# openTPM-v20.net
KiCad netlist of a schematic drawn in EAGLE
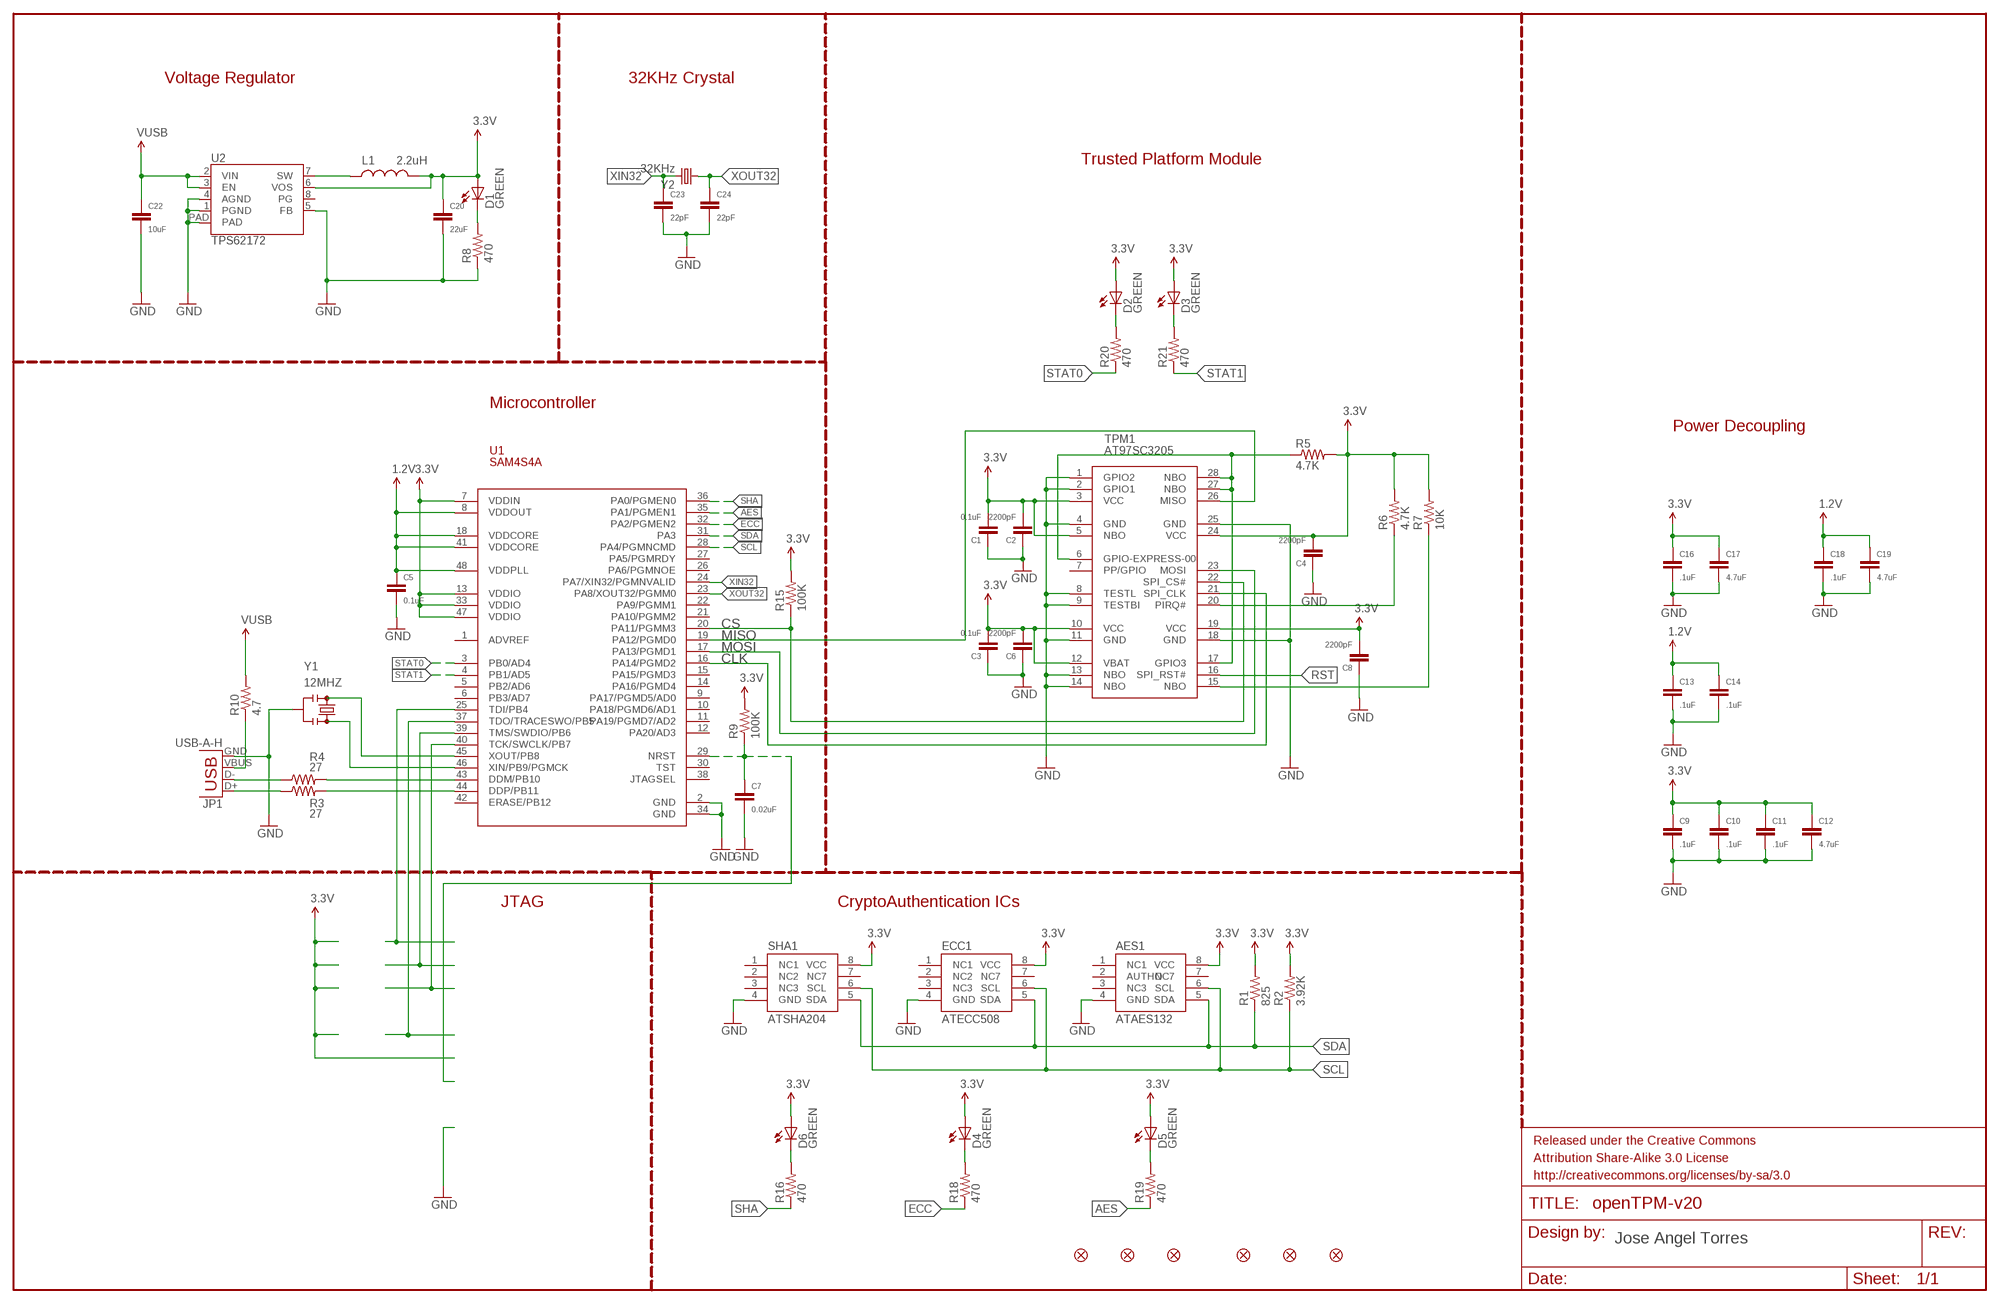
[diagram p0: schematic, sheet 1]

(export (version "E")
  (design (tool "Eeschema 10.0.6"))
  (components
    (comp (ref "AES1")
      (value "ATAES132")
      (footprint "eagle-import:CRYPTOTRONIX_SOIC8")
      (libsource (lib "eagle-import") (part "CRYPTOTRONIX_ATAES132"))
    )
    (comp (ref "C1")
      (value "0.1uF")
      (footprint "eagle-import:0402")
      (libsource (lib "eagle-import") (part "CAPACITOR.0402"))
    )
    (comp (ref "C2")
      (value "2200pF")
      (footprint "eagle-import:0402")
      (libsource (lib "eagle-import") (part "CAPACITOR.0402"))
    )
    (comp (ref "C3")
      (value "0.1uF")
      (footprint "eagle-import:0402")
      (libsource (lib "eagle-import") (part "CAPACITOR.0402"))
    )
    (comp (ref "C4")
      (value "2200pF")
      (footprint "eagle-import:0402")
      (libsource (lib "eagle-import") (part "CAPACITOR.0402"))
    )
    (comp (ref "C5")
      (value "0.1uF")
      (footprint "eagle-import:0402")
      (libsource (lib "eagle-import") (part "CAPACITOR.0402"))
    )
    (comp (ref "C6")
      (value "2200pF")
      (footprint "eagle-import:0402")
      (libsource (lib "eagle-import") (part "CAPACITOR.0402"))
    )
    (comp (ref "C7")
      (value "0.02uF")
      (footprint "eagle-import:0402")
      (libsource (lib "eagle-import") (part "CAPACITOR.0402"))
    )
    (comp (ref "C8")
      (value "2200pF")
      (footprint "eagle-import:0402")
      (libsource (lib "eagle-import") (part "CAPACITOR.0402"))
    )
    (comp (ref "C9")
      (value ".1uF")
      (footprint "eagle-import:0402")
      (libsource (lib "eagle-import") (part "CAPACITOR.0402"))
    )
    (comp (ref "C10")
      (value ".1uF")
      (footprint "eagle-import:0402")
      (libsource (lib "eagle-import") (part "CAPACITOR.0402"))
    )
    (comp (ref "C11")
      (value ".1uF")
      (footprint "eagle-import:0402")
      (libsource (lib "eagle-import") (part "CAPACITOR.0402"))
    )
    (comp (ref "C12")
      (value "4.7uF")
      (footprint "eagle-import:0402")
      (libsource (lib "eagle-import") (part "CAPACITOR.0402"))
    )
    (comp (ref "C13")
      (value ".1uF")
      (footprint "eagle-import:0402")
      (libsource (lib "eagle-import") (part "CAPACITOR.0402"))
    )
    (comp (ref "C14")
      (value ".1uF")
      (footprint "eagle-import:0402")
      (libsource (lib "eagle-import") (part "CAPACITOR.0402"))
    )
    (comp (ref "C16")
      (value ".1uF")
      (footprint "eagle-import:0402")
      (libsource (lib "eagle-import") (part "CAPACITOR.0402"))
    )
    (comp (ref "C17")
      (value "4.7uF")
      (footprint "eagle-import:0402")
      (libsource (lib "eagle-import") (part "CAPACITOR.0402"))
    )
    (comp (ref "C18")
      (value ".1uF")
      (footprint "eagle-import:0402")
      (libsource (lib "eagle-import") (part "CAPACITOR.0402"))
    )
    (comp (ref "C19")
      (value "4.7uF")
      (footprint "eagle-import:0402")
      (libsource (lib "eagle-import") (part "CAPACITOR.0402"))
    )
    (comp (ref "C20")
      (value "22uF")
      (footprint "eagle-import:0603")
      (libsource (lib "eagle-import") (part "CAPACITOR.0603"))
    )
    (comp (ref "C22")
      (value "10uF")
      (footprint "eagle-import:0402")
      (libsource (lib "eagle-import") (part "CAPACITOR.0402"))
    )
    (comp (ref "C23")
      (value "22pF")
      (footprint "eagle-import:0402")
      (libsource (lib "eagle-import") (part "CAPACITOR.0402"))
    )
    (comp (ref "C24")
      (value "22pF")
      (footprint "eagle-import:0402")
      (libsource (lib "eagle-import") (part "CAPACITOR.0402"))
    )
    (comp (ref "D1")
      (value "GREEN")
      (footprint "eagle-import:SPARKFUN-LED_LED-0603")
      (libsource (lib "eagle-import") (part "SPARKFUN-LED_LED-GREEN0603"))
    )
    (comp (ref "D2")
      (value "GREEN")
      (footprint "eagle-import:SPARKFUN-LED_LED-0603")
      (libsource (lib "eagle-import") (part "SPARKFUN-LED_LED-GREEN0603"))
    )
    (comp (ref "D3")
      (value "GREEN")
      (footprint "eagle-import:SPARKFUN-LED_LED-0603")
      (libsource (lib "eagle-import") (part "SPARKFUN-LED_LED-GREEN0603"))
    )
    (comp (ref "D4")
      (value "GREEN")
      (footprint "eagle-import:SPARKFUN-LED_LED-0603")
      (libsource (lib "eagle-import") (part "SPARKFUN-LED_LED-GREEN0603"))
    )
    (comp (ref "D5")
      (value "GREEN")
      (footprint "eagle-import:SPARKFUN-LED_LED-0603")
      (libsource (lib "eagle-import") (part "SPARKFUN-LED_LED-GREEN0603"))
    )
    (comp (ref "D6")
      (value "GREEN")
      (footprint "eagle-import:SPARKFUN-LED_LED-0603")
      (libsource (lib "eagle-import") (part "SPARKFUN-LED_LED-GREEN0603"))
    )
    (comp (ref "ECC1")
      (value "ATECC508")
      (footprint "eagle-import:CRYPTOTRONIX_SOIC8")
      (libsource (lib "eagle-import") (part "ATECC508"))
    )
    (comp (ref "FID1")
      (value "SPARKFUN-AESTHETICS_FIDUCIAL1X2")
      (footprint "eagle-import:SPARKFUN-AESTHETICS_FIDUCIAL-1X2")
      (libsource (lib "eagle-import") (part "SPARKFUN-AESTHETICS_FIDUCIAL1X2"))
    )
    (comp (ref "FID2")
      (value "SPARKFUN-AESTHETICS_FIDUCIAL1X2")
      (footprint "eagle-import:SPARKFUN-AESTHETICS_FIDUCIAL-1X2")
      (libsource (lib "eagle-import") (part "SPARKFUN-AESTHETICS_FIDUCIAL1X2"))
    )
    (comp (ref "FID3")
      (value "SPARKFUN-AESTHETICS_FIDUCIAL1X2")
      (footprint "eagle-import:SPARKFUN-AESTHETICS_FIDUCIAL-1X2")
      (libsource (lib "eagle-import") (part "SPARKFUN-AESTHETICS_FIDUCIAL1X2"))
    )
    (comp (ref "FID4")
      (value "SPARKFUN-AESTHETICS_FIDUCIAL1X2")
      (footprint "eagle-import:SPARKFUN-AESTHETICS_FIDUCIAL-1X2")
      (libsource (lib "eagle-import") (part "SPARKFUN-AESTHETICS_FIDUCIAL1X2"))
    )
    (comp (ref "FID5")
      (value "SPARKFUN-AESTHETICS_FIDUCIAL1X2")
      (footprint "eagle-import:SPARKFUN-AESTHETICS_FIDUCIAL-1X2")
      (libsource (lib "eagle-import") (part "SPARKFUN-AESTHETICS_FIDUCIAL1X2"))
    )
    (comp (ref "FID6")
      (value "SPARKFUN-AESTHETICS_FIDUCIAL1X2")
      (footprint "eagle-import:SPARKFUN-AESTHETICS_FIDUCIAL-1X2")
      (libsource (lib "eagle-import") (part "SPARKFUN-AESTHETICS_FIDUCIAL1X2"))
    )
    (comp (ref "JP1")
      (value "USB-A-H")
      (footprint "eagle-import:USB-A-H")
      (libsource (lib "eagle-import") (part "USB-A-H"))
    )
    (comp (ref "L1")
      (value "2.2uH")
      (footprint "eagle-import:C0402")
      (libsource (lib "eagle-import") (part "INDUCTOR0402"))
    )
    (comp (ref "R1")
      (value "825")
      (footprint "eagle-import:0402")
      (libsource (lib "eagle-import") (part "RESISTOR.0402"))
    )
    (comp (ref "R2")
      (value "3.92K")
      (footprint "eagle-import:0402")
      (libsource (lib "eagle-import") (part "RESISTOR.0402"))
    )
    (comp (ref "R3")
      (value "27")
      (footprint "eagle-import:0402")
      (libsource (lib "eagle-import") (part "RESISTOR.0402"))
    )
    (comp (ref "R4")
      (value "27")
      (footprint "eagle-import:0402")
      (libsource (lib "eagle-import") (part "RESISTOR.0402"))
    )
    (comp (ref "R5")
      (value "4.7K")
      (footprint "eagle-import:0402")
      (libsource (lib "eagle-import") (part "RESISTOR.0402"))
    )
    (comp (ref "R6")
      (value "4.7K")
      (footprint "eagle-import:0402")
      (libsource (lib "eagle-import") (part "RESISTOR.0402"))
    )
    (comp (ref "R7")
      (value "10K")
      (footprint "eagle-import:0402")
      (libsource (lib "eagle-import") (part "RESISTOR.0402"))
    )
    (comp (ref "R8")
      (value "470")
      (footprint "eagle-import:0402")
      (libsource (lib "eagle-import") (part "RESISTOR.0402"))
    )
    (comp (ref "R9")
      (value "100K")
      (footprint "eagle-import:0402")
      (libsource (lib "eagle-import") (part "RESISTOR.0402"))
    )
    (comp (ref "R10")
      (value "4.7")
      (footprint "eagle-import:0402")
      (libsource (lib "eagle-import") (part "RESISTOR.0402"))
    )
    (comp (ref "R15")
      (value "100K")
      (footprint "eagle-import:0402")
      (libsource (lib "eagle-import") (part "RESISTOR.0402"))
    )
    (comp (ref "R16")
      (value "470")
      (footprint "eagle-import:0402")
      (libsource (lib "eagle-import") (part "RESISTOR.0402"))
    )
    (comp (ref "R18")
      (value "470")
      (footprint "eagle-import:0402")
      (libsource (lib "eagle-import") (part "RESISTOR.0402"))
    )
    (comp (ref "R19")
      (value "470")
      (footprint "eagle-import:0402")
      (libsource (lib "eagle-import") (part "RESISTOR.0402"))
    )
    (comp (ref "R20")
      (value "470")
      (footprint "eagle-import:0402")
      (libsource (lib "eagle-import") (part "RESISTOR.0402"))
    )
    (comp (ref "R21")
      (value "470")
      (footprint "eagle-import:0402")
      (libsource (lib "eagle-import") (part "RESISTOR.0402"))
    )
    (comp (ref "SHA1")
      (value "ATSHA204")
      (footprint "eagle-import:CRYPTOTRONIX_SOIC8")
      (libsource (lib "eagle-import") (part "CRYPTOTRONIX_ATSHA204"))
    )
    (comp (ref "TPM1")
      (value "AT97SC3205")
      (footprint "eagle-import:TSSOP28")
      (libsource (lib "eagle-import") (part "AT97SC3205"))
    )
    (comp (ref "U1")
      (value "SAM4S4A")
      (footprint "eagle-import:LQFP-48")
      (libsource (lib "eagle-import") (part "SAM4S4A"))
    )
    (comp (ref "U2")
      (value "TPS62172")
      (footprint "eagle-import:WSON-8-PAD")
      (libsource (lib "eagle-import") (part "TPS62172"))
    )
    (comp (ref "Y1")
      (value "12MHZ")
      (footprint "eagle-import:RESONATOR-SMD")
      (libsource (lib "eagle-import") (part "RESONATOR12MHZ"))
    )
    (comp (ref "Y2")
      (value "32KHz")
      (footprint "eagle-import:CRYSTAL-32KHZ-SMD_EPSON_MC146")
      (libsource (lib "eagle-import") (part "CRYSTALEPSONMC146"))
    )
  )
  (nets
    (net (code "1") (name "/CLK") (class "Default")
      (node (ref "TPM1") (pin "21") (pinfunction "SPI_CLK_21") (pintype "bidirectional"))
      (node (ref "U1") (pin "16") (pinfunction "PA14/PGMD2_16") (pintype "bidirectional"))
    )
    (net (code "2") (name "/CS") (class "Default")
      (node (ref "R15") (pin "1") (pinfunction "1_1") (pintype "passive"))
      (node (ref "TPM1") (pin "22") (pinfunction "SPI_CS#_22") (pintype "power_in"))
      (node (ref "U1") (pin "20") (pinfunction "PA11/PGMM3_20") (pintype "bidirectional"))
    )
    (net (code "3") (name "/MISO") (class "Default")
      (node (ref "TPM1") (pin "26") (pinfunction "MISO_26") (pintype "power_in"))
      (node (ref "U1") (pin "19") (pinfunction "PA12/PGMD0_19") (pintype "bidirectional"))
    )
    (net (code "4") (name "/MOSI") (class "Default")
      (node (ref "TPM1") (pin "23") (pinfunction "MOSI_23") (pintype "power_in"))
      (node (ref "U1") (pin "17") (pinfunction "PA13/PGMD1_17") (pintype "bidirectional"))
    )
    (net (code "5") (name "1.2V") (class "Default")
      (node (ref "C13") (pin "1") (pinfunction "1_1") (pintype "passive"))
      (node (ref "C14") (pin "1") (pinfunction "1_1") (pintype "passive"))
      (node (ref "C18") (pin "1") (pinfunction "1_1") (pintype "passive"))
      (node (ref "C19") (pin "1") (pinfunction "1_1") (pintype "passive"))
      (node (ref "C5") (pin "1") (pinfunction "1_1") (pintype "passive"))
      (node (ref "U1") (pin "18") (pinfunction "VDDCORE_18") (pintype "bidirectional"))
      (node (ref "U1") (pin "41") (pinfunction "VDDCORE_41") (pintype "bidirectional"))
      (node (ref "U1") (pin "48") (pinfunction "VDDPLL_48") (pintype "bidirectional"))
      (node (ref "U1") (pin "8") (pinfunction "VDDOUT_8") (pintype "bidirectional"))
    )
    (net (code "6") (name "3.3V") (class "Default")
      (node (ref "AES1") (pin "8") (pinfunction "VCC_8") (pintype "power_in"))
      (node (ref "C1") (pin "2") (pinfunction "2_2") (pintype "passive"))
      (node (ref "C10") (pin "1") (pinfunction "1_1") (pintype "passive"))
      (node (ref "C11") (pin "1") (pinfunction "1_1") (pintype "passive"))
      (node (ref "C12") (pin "1") (pinfunction "1_1") (pintype "passive"))
      (node (ref "C16") (pin "1") (pinfunction "1_1") (pintype "passive"))
      (node (ref "C17") (pin "1") (pinfunction "1_1") (pintype "passive"))
      (node (ref "C2") (pin "2") (pinfunction "2_2") (pintype "passive"))
      (node (ref "C20") (pin "1") (pinfunction "1_1") (pintype "passive"))
      (node (ref "C3") (pin "2") (pinfunction "2_2") (pintype "passive"))
      (node (ref "C4") (pin "2") (pinfunction "2_2") (pintype "passive"))
      (node (ref "C6") (pin "2") (pinfunction "2_2") (pintype "passive"))
      (node (ref "C8") (pin "2") (pinfunction "2_2") (pintype "passive"))
      (node (ref "C9") (pin "1") (pinfunction "1_1") (pintype "passive"))
      (node (ref "D1") (pin "A") (pinfunction "A_A") (pintype "passive"))
      (node (ref "D2") (pin "A") (pinfunction "A_A") (pintype "passive"))
      (node (ref "D3") (pin "A") (pinfunction "A_A") (pintype "passive"))
      (node (ref "D4") (pin "A") (pinfunction "A_A") (pintype "passive"))
      (node (ref "D5") (pin "A") (pinfunction "A_A") (pintype "passive"))
      (node (ref "D6") (pin "A") (pinfunction "A_A") (pintype "passive"))
      (node (ref "ECC1") (pin "8") (pinfunction "VCC_8") (pintype "power_in"))
      (node (ref "L1") (pin "2") (pinfunction "2_2") (pintype "passive"))
      (node (ref "R1") (pin "2") (pinfunction "2_2") (pintype "passive"))
      (node (ref "R15") (pin "2") (pinfunction "2_2") (pintype "passive"))
      (node (ref "R2") (pin "2") (pinfunction "2_2") (pintype "passive"))
      (node (ref "R5") (pin "2") (pinfunction "2_2") (pintype "passive"))
      (node (ref "R6") (pin "2") (pinfunction "2_2") (pintype "passive"))
      (node (ref "R7") (pin "2") (pinfunction "2_2") (pintype "passive"))
      (node (ref "R9") (pin "2") (pinfunction "2_2") (pintype "passive"))
      (node (ref "SHA1") (pin "8") (pinfunction "VCC_8") (pintype "power_in"))
      (node (ref "TPM1") (pin "10") (pinfunction "VCC_10") (pintype "power_in"))
      (node (ref "TPM1") (pin "12") (pinfunction "VBAT_12") (pintype "bidirectional"))
      (node (ref "TPM1") (pin "19") (pinfunction "VCC_19") (pintype "power_in"))
      (node (ref "TPM1") (pin "24") (pinfunction "VCC_24") (pintype "power_in"))
      (node (ref "TPM1") (pin "3") (pinfunction "VCC_3") (pintype "power_in"))
      (node (ref "TPM1") (pin "5") (pinfunction "NBO_5") (pintype "bidirectional"))
      (node (ref "U1") (pin "13") (pinfunction "VDDIO_13") (pintype "bidirectional"))
      (node (ref "U1") (pin "33") (pinfunction "VDDIO_33") (pintype "bidirectional"))
      (node (ref "U1") (pin "47") (pinfunction "VDDIO_47") (pintype "bidirectional"))
      (node (ref "U1") (pin "7") (pinfunction "VDDIN_7") (pintype "bidirectional"))
      (node (ref "U2") (pin "6") (pinfunction "VOS_6") (pintype "bidirectional"))
    )
    (net (code "7") (name "AES") (class "Default")
      (node (ref "R19") (pin "1") (pinfunction "1_1") (pintype "passive"))
      (node (ref "U1") (pin "35") (pinfunction "PA1/PGMEN1_35") (pintype "bidirectional"))
    )
    (net (code "8") (name "ECC") (class "Default")
      (node (ref "R18") (pin "1") (pinfunction "1_1") (pintype "passive"))
      (node (ref "U1") (pin "32") (pinfunction "PA2/PGMEN2_32") (pintype "bidirectional"))
    )
    (net (code "9") (name "GND") (class "Default")
      (node (ref "AES1") (pin "4") (pinfunction "GND_4") (pintype "power_in"))
      (node (ref "C1") (pin "1") (pinfunction "1_1") (pintype "passive"))
      (node (ref "C10") (pin "2") (pinfunction "2_2") (pintype "passive"))
      (node (ref "C11") (pin "2") (pinfunction "2_2") (pintype "passive"))
      (node (ref "C12") (pin "2") (pinfunction "2_2") (pintype "passive"))
      (node (ref "C13") (pin "2") (pinfunction "2_2") (pintype "passive"))
      (node (ref "C14") (pin "2") (pinfunction "2_2") (pintype "passive"))
      (node (ref "C16") (pin "2") (pinfunction "2_2") (pintype "passive"))
      (node (ref "C17") (pin "2") (pinfunction "2_2") (pintype "passive"))
      (node (ref "C18") (pin "2") (pinfunction "2_2") (pintype "passive"))
      (node (ref "C19") (pin "2") (pinfunction "2_2") (pintype "passive"))
      (node (ref "C2") (pin "1") (pinfunction "1_1") (pintype "passive"))
      (node (ref "C20") (pin "2") (pinfunction "2_2") (pintype "passive"))
      (node (ref "C22") (pin "2") (pinfunction "2_2") (pintype "passive"))
      (node (ref "C23") (pin "2") (pinfunction "2_2") (pintype "passive"))
      (node (ref "C24") (pin "2") (pinfunction "2_2") (pintype "passive"))
      (node (ref "C3") (pin "1") (pinfunction "1_1") (pintype "passive"))
      (node (ref "C4") (pin "1") (pinfunction "1_1") (pintype "passive"))
      (node (ref "C5") (pin "2") (pinfunction "2_2") (pintype "passive"))
      (node (ref "C6") (pin "1") (pinfunction "1_1") (pintype "passive"))
      (node (ref "C7") (pin "2") (pinfunction "2_2") (pintype "passive"))
      (node (ref "C8") (pin "1") (pinfunction "1_1") (pintype "passive"))
      (node (ref "C9") (pin "2") (pinfunction "2_2") (pintype "passive"))
      (node (ref "ECC1") (pin "4") (pinfunction "GND_4") (pintype "power_in"))
      (node (ref "JP1") (pin "GND") (pinfunction "GND_GND") (pintype "bidirectional"))
      (node (ref "R8") (pin "1") (pinfunction "1_1") (pintype "passive"))
      (node (ref "SHA1") (pin "4") (pinfunction "GND_4") (pintype "power_in"))
      (node (ref "TPM1") (pin "1") (pinfunction "GPIO2_1") (pintype "bidirectional"))
      (node (ref "TPM1") (pin "11") (pinfunction "GND_11") (pintype "power_in"))
      (node (ref "TPM1") (pin "13") (pinfunction "NBO_13") (pintype "bidirectional"))
      (node (ref "TPM1") (pin "14") (pinfunction "NBO_14") (pintype "bidirectional"))
      (node (ref "TPM1") (pin "18") (pinfunction "GND_18") (pintype "power_in"))
      (node (ref "TPM1") (pin "2") (pinfunction "GPIO1_2") (pintype "bidirectional"))
      (node (ref "TPM1") (pin "25") (pinfunction "GND_25") (pintype "power_in"))
      (node (ref "TPM1") (pin "4") (pinfunction "GND_4") (pintype "power_in"))
      (node (ref "TPM1") (pin "8") (pinfunction "TESTL_8") (pintype "bidirectional"))
      (node (ref "TPM1") (pin "9") (pinfunction "TESTBI_9") (pintype "bidirectional"))
      (node (ref "U1") (pin "2") (pinfunction "GND_2") (pintype "bidirectional"))
      (node (ref "U1") (pin "34") (pinfunction "GND_34") (pintype "bidirectional"))
      (node (ref "U2") (pin "1") (pinfunction "PGND_1") (pintype "bidirectional"))
      (node (ref "U2") (pin "4") (pinfunction "AGND_4") (pintype "bidirectional"))
      (node (ref "U2") (pin "5") (pinfunction "FB_5") (pintype "bidirectional"))
      (node (ref "U2") (pin "PAD") (pinfunction "PAD_PAD") (pintype "bidirectional"))
      (node (ref "Y1") (pin "2") (pinfunction "2_2") (pintype "passive"))
    )
    (net (code "10") (name "Net-(D1-PadC)") (class "Default")
      (node (ref "D1") (pin "C") (pinfunction "C_C") (pintype "passive"))
      (node (ref "R8") (pin "2") (pinfunction "2_2") (pintype "passive"))
    )
    (net (code "11") (name "Net-(D2-PadC)") (class "Default")
      (node (ref "D2") (pin "C") (pinfunction "C_C") (pintype "passive"))
      (node (ref "R20") (pin "2") (pinfunction "2_2") (pintype "passive"))
    )
    (net (code "12") (name "Net-(D3-PadC)") (class "Default")
      (node (ref "D3") (pin "C") (pinfunction "C_C") (pintype "passive"))
      (node (ref "R21") (pin "2") (pinfunction "2_2") (pintype "passive"))
    )
    (net (code "13") (name "Net-(D4-PadC)") (class "Default")
      (node (ref "D4") (pin "C") (pinfunction "C_C") (pintype "passive"))
      (node (ref "R18") (pin "2") (pinfunction "2_2") (pintype "passive"))
    )
    (net (code "14") (name "Net-(D5-PadC)") (class "Default")
      (node (ref "D5") (pin "C") (pinfunction "C_C") (pintype "passive"))
      (node (ref "R19") (pin "2") (pinfunction "2_2") (pintype "passive"))
    )
    (net (code "15") (name "Net-(D6-PadC)") (class "Default")
      (node (ref "D6") (pin "C") (pinfunction "C_C") (pintype "passive"))
      (node (ref "R16") (pin "2") (pinfunction "2_2") (pintype "passive"))
    )
    (net (code "16") (name "Net-(JP1-PadD+)") (class "Default")
      (node (ref "JP1") (pin "D+") (pinfunction "D+_D+") (pintype "bidirectional"))
      (node (ref "R3") (pin "1") (pinfunction "1_1") (pintype "passive"))
    )
    (net (code "17") (name "Net-(JP1-PadD-)") (class "Default")
      (node (ref "JP1") (pin "D-") (pinfunction "D-_D-") (pintype "bidirectional"))
      (node (ref "R4") (pin "1") (pinfunction "1_1") (pintype "passive"))
    )
    (net (code "18") (name "Net-(JP1-PadVBUS)") (class "Default")
      (node (ref "JP1") (pin "VBUS") (pinfunction "VBUS_VBUS") (pintype "bidirectional"))
      (node (ref "R10") (pin "1") (pinfunction "1_1") (pintype "passive"))
    )
    (net (code "19") (name "Net-(R7-Pad1)") (class "Default")
      (node (ref "R7") (pin "1") (pinfunction "1_1") (pintype "passive"))
      (node (ref "TPM1") (pin "15") (pinfunction "NBO_15") (pintype "bidirectional"))
    )
    (net (code "20") (name "Net-(TPM1-GPIO-EXPRESS-00)") (class "Default")
      (node (ref "R5") (pin "1") (pinfunction "1_1") (pintype "passive"))
      (node (ref "TPM1") (pin "17") (pinfunction "GPIO3_17") (pintype "power_in"))
      (node (ref "TPM1") (pin "27") (pinfunction "NBO_27") (pintype "bidirectional"))
      (node (ref "TPM1") (pin "28") (pinfunction "NBO_28") (pintype "bidirectional"))
      (node (ref "TPM1") (pin "6") (pinfunction "GPIO-EXPRESS-00_6") (pintype "power_in"))
    )
    (net (code "21") (name "Net-(TPM1-PIRQ#)") (class "Default")
      (node (ref "R6") (pin "1") (pinfunction "1_1") (pintype "passive"))
      (node (ref "TPM1") (pin "20") (pinfunction "PIRQ#_20") (pintype "power_in"))
    )
    (net (code "22") (name "Net-(U1-DDM{slash}PB10)") (class "Default")
      (node (ref "R4") (pin "2") (pinfunction "2_2") (pintype "passive"))
      (node (ref "U1") (pin "43") (pinfunction "DDM/PB10_43") (pintype "bidirectional"))
    )
    (net (code "23") (name "Net-(U1-DDP{slash}PB11)") (class "Default")
      (node (ref "R3") (pin "2") (pinfunction "2_2") (pintype "passive"))
      (node (ref "U1") (pin "44") (pinfunction "DDP/PB11_44") (pintype "bidirectional"))
    )
    (net (code "24") (name "Net-(U1-XIN{slash}PB9{slash}PGMCK)") (class "Default")
      (node (ref "U1") (pin "46") (pinfunction "XIN/PB9/PGMCK_46") (pintype "bidirectional"))
      (node (ref "Y1") (pin "3") (pinfunction "3_3") (pintype "passive"))
    )
    (net (code "25") (name "Net-(U1-XOUT{slash}PB8)") (class "Default")
      (node (ref "U1") (pin "45") (pinfunction "XOUT/PB8_45") (pintype "bidirectional"))
      (node (ref "Y1") (pin "1") (pinfunction "1_1") (pintype "passive"))
    )
    (net (code "26") (name "Net-(U2-SW)") (class "Default")
      (node (ref "L1") (pin "1") (pinfunction "1_1") (pintype "passive"))
      (node (ref "U2") (pin "7") (pinfunction "SW_7") (pintype "bidirectional"))
    )
    (net (code "27") (name "RST") (class "Default")
      (node (ref "C7") (pin "1") (pinfunction "1_1") (pintype "passive"))
      (node (ref "R9") (pin "1") (pinfunction "1_1") (pintype "passive"))
      (node (ref "TPM1") (pin "16") (pinfunction "SPI_RST#_16") (pintype "bidirectional"))
      (node (ref "U1") (pin "29") (pinfunction "NRST_29") (pintype "bidirectional"))
    )
    (net (code "28") (name "SCL") (class "Default")
      (node (ref "AES1") (pin "6") (pinfunction "SCL_6") (pintype "bidirectional"))
      (node (ref "ECC1") (pin "6") (pinfunction "SCL_6") (pintype "bidirectional"))
      (node (ref "R2") (pin "1") (pinfunction "1_1") (pintype "passive"))
      (node (ref "SHA1") (pin "6") (pinfunction "SCL_6") (pintype "bidirectional"))
      (node (ref "U1") (pin "28") (pinfunction "PA4/PGMNCMD_28") (pintype "bidirectional"))
    )
    (net (code "29") (name "SDA") (class "Default")
      (node (ref "AES1") (pin "5") (pinfunction "SDA_5") (pintype "bidirectional"))
      (node (ref "ECC1") (pin "5") (pinfunction "SDA_5") (pintype "bidirectional"))
      (node (ref "R1") (pin "1") (pinfunction "1_1") (pintype "passive"))
      (node (ref "SHA1") (pin "5") (pinfunction "SDA_5") (pintype "bidirectional"))
      (node (ref "U1") (pin "31") (pinfunction "PA3_31") (pintype "bidirectional"))
    )
    (net (code "30") (name "SHA") (class "Default")
      (node (ref "R16") (pin "1") (pinfunction "1_1") (pintype "passive"))
      (node (ref "U1") (pin "36") (pinfunction "PA0/PGMEN0_36") (pintype "bidirectional"))
    )
    (net (code "31") (name "STAT0") (class "Default")
      (node (ref "R20") (pin "1") (pinfunction "1_1") (pintype "passive"))
      (node (ref "U1") (pin "3") (pinfunction "PB0/AD4_3") (pintype "bidirectional"))
    )
    (net (code "32") (name "STAT1") (class "Default")
      (node (ref "R21") (pin "1") (pinfunction "1_1") (pintype "passive"))
      (node (ref "U1") (pin "4") (pinfunction "PB1/AD5_4") (pintype "bidirectional"))
    )
    (net (code "33") (name "VUSB") (class "Default")
      (node (ref "C22") (pin "1") (pinfunction "1_1") (pintype "passive"))
      (node (ref "R10") (pin "2") (pinfunction "2_2") (pintype "passive"))
      (node (ref "U2") (pin "2") (pinfunction "VIN_2") (pintype "bidirectional"))
      (node (ref "U2") (pin "3") (pinfunction "EN_3") (pintype "bidirectional"))
    )
    (net (code "34") (name "XIN32") (class "Default")
      (node (ref "C23") (pin "1") (pinfunction "1_1") (pintype "passive"))
      (node (ref "U1") (pin "24") (pinfunction "PA7/XIN32/PGMNVALID_24") (pintype "bidirectional"))
      (node (ref "Y2") (pin "P$1") (pinfunction "2_P$1") (pintype "passive"))
    )
    (net (code "35") (name "XOUT32") (class "Default")
      (node (ref "C24") (pin "1") (pinfunction "1_1") (pintype "passive"))
      (node (ref "U1") (pin "23") (pinfunction "PA8/XOUT32/PGMM0_23") (pintype "bidirectional"))
      (node (ref "Y2") (pin "P$2") (pinfunction "1_P$2") (pintype "passive"))
    )
    (net (code "36") (name "unconnected-(AES1-AUTHO-Pad2)") (class "Default")
      (node (ref "AES1") (pin "2") (pinfunction "AUTHO_2") (pintype "bidirectional"))
    )
    (net (code "37") (name "unconnected-(AES1-NC1-Pad1)") (class "Default")
      (node (ref "AES1") (pin "1") (pinfunction "NC1_1") (pintype "no_connect"))
    )
    (net (code "38") (name "unconnected-(AES1-NC3-Pad3)") (class "Default")
      (node (ref "AES1") (pin "3") (pinfunction "NC3_3") (pintype "no_connect"))
    )
    (net (code "39") (name "unconnected-(AES1-NC7-Pad7)") (class "Default")
      (node (ref "AES1") (pin "7") (pinfunction "NC7_7") (pintype "no_connect"))
    )
    (net (code "40") (name "unconnected-(ECC1-NC1-Pad1)") (class "Default")
      (node (ref "ECC1") (pin "1") (pinfunction "NC1_1") (pintype "bidirectional"))
    )
    (net (code "41") (name "unconnected-(ECC1-NC2-Pad2)") (class "Default")
      (node (ref "ECC1") (pin "2") (pinfunction "NC2_2") (pintype "no_connect"))
    )
    (net (code "42") (name "unconnected-(ECC1-NC3-Pad3)") (class "Default")
      (node (ref "ECC1") (pin "3") (pinfunction "NC3_3") (pintype "no_connect"))
    )
    (net (code "43") (name "unconnected-(ECC1-NC7-Pad7)") (class "Default")
      (node (ref "ECC1") (pin "7") (pinfunction "NC7_7") (pintype "no_connect"))
    )
    (net (code "44") (name "unconnected-(SHA1-NC1-Pad1)") (class "Default")
      (node (ref "SHA1") (pin "1") (pinfunction "NC1_1") (pintype "no_connect"))
    )
    (net (code "45") (name "unconnected-(SHA1-NC2-Pad2)") (class "Default")
      (node (ref "SHA1") (pin "2") (pinfunction "NC2_2") (pintype "no_connect"))
    )
    (net (code "46") (name "unconnected-(SHA1-NC3-Pad3)") (class "Default")
      (node (ref "SHA1") (pin "3") (pinfunction "NC3_3") (pintype "no_connect"))
    )
    (net (code "47") (name "unconnected-(SHA1-NC7-Pad7)") (class "Default")
      (node (ref "SHA1") (pin "7") (pinfunction "NC7_7") (pintype "no_connect"))
    )
    (net (code "48") (name "unconnected-(TPM1-PP{slash}GPIO-Pad7)") (class "Default")
      (node (ref "TPM1") (pin "7") (pinfunction "PP/GPIO_7") (pintype "bidirectional"))
    )
    (net (code "49") (name "unconnected-(U1-ADVREF-Pad1)") (class "Default")
      (node (ref "U1") (pin "1") (pinfunction "ADVREF_1") (pintype "bidirectional"))
    )
    (net (code "50") (name "unconnected-(U1-ERASE{slash}PB12-Pad42)") (class "Default")
      (node (ref "U1") (pin "42") (pinfunction "ERASE/PB12_42") (pintype "bidirectional"))
    )
    (net (code "51") (name "unconnected-(U1-JTAGSEL-Pad38)") (class "Default")
      (node (ref "U1") (pin "38") (pinfunction "JTAGSEL_38") (pintype "bidirectional"))
    )
    (net (code "52") (name "unconnected-(U1-PA5{slash}PGMRDY-Pad27)") (class "Default")
      (node (ref "U1") (pin "27") (pinfunction "PA5/PGMRDY_27") (pintype "bidirectional"))
    )
    (net (code "53") (name "unconnected-(U1-PA6{slash}PGMNOE-Pad26)") (class "Default")
      (node (ref "U1") (pin "26") (pinfunction "PA6/PGMNOE_26") (pintype "bidirectional"))
    )
    (net (code "54") (name "unconnected-(U1-PA9{slash}PGMM1-Pad22)") (class "Default")
      (node (ref "U1") (pin "22") (pinfunction "PA9/PGMM1_22") (pintype "bidirectional"))
    )
    (net (code "55") (name "unconnected-(U1-PA10{slash}PGMM2-Pad21)") (class "Default")
      (node (ref "U1") (pin "21") (pinfunction "PA10/PGMM2_21") (pintype "bidirectional"))
    )
    (net (code "56") (name "unconnected-(U1-PA15{slash}PGMD3-Pad15)") (class "Default")
      (node (ref "U1") (pin "15") (pinfunction "PA15/PGMD3_15") (pintype "bidirectional"))
    )
    (net (code "57") (name "unconnected-(U1-PA16{slash}PGMD4-Pad14)") (class "Default")
      (node (ref "U1") (pin "14") (pinfunction "PA16/PGMD4_14") (pintype "bidirectional"))
    )
    (net (code "58") (name "unconnected-(U1-PA17{slash}PGMD5{slash}AD0-Pad9)") (class "Default")
      (node (ref "U1") (pin "9") (pinfunction "PA17/PGMD5/AD0_9") (pintype "bidirectional"))
    )
    (net (code "59") (name "unconnected-(U1-PA18{slash}PGMD6{slash}AD1-Pad10)") (class "Default")
      (node (ref "U1") (pin "10") (pinfunction "PA18/PGMD6/AD1_10") (pintype "bidirectional"))
    )
    (net (code "60") (name "unconnected-(U1-PA19{slash}PGMD7{slash}AD2-Pad11)") (class "Default")
      (node (ref "U1") (pin "11") (pinfunction "PA19/PGMD7/AD2_11") (pintype "bidirectional"))
    )
    (net (code "61") (name "unconnected-(U1-PA20{slash}AD3-Pad12)") (class "Default")
      (node (ref "U1") (pin "12") (pinfunction "PA20/AD3_12") (pintype "bidirectional"))
    )
    (net (code "62") (name "unconnected-(U1-PB2{slash}AD6-Pad5)") (class "Default")
      (node (ref "U1") (pin "5") (pinfunction "PB2/AD6_5") (pintype "bidirectional"))
    )
    (net (code "63") (name "unconnected-(U1-PB3{slash}AD7-Pad6)") (class "Default")
      (node (ref "U1") (pin "6") (pinfunction "PB3/AD7_6") (pintype "bidirectional"))
    )
    (net (code "64") (name "unconnected-(U1-TCK{slash}SWCLK{slash}PB7-Pad40)") (class "Default")
      (node (ref "U1") (pin "40") (pinfunction "TCK/SWCLK/PB7_40") (pintype "bidirectional"))
    )
    (net (code "65") (name "unconnected-(U1-TDI{slash}PB4-Pad25)") (class "Default")
      (node (ref "U1") (pin "25") (pinfunction "TDI/PB4_25") (pintype "bidirectional"))
    )
    (net (code "66") (name "unconnected-(U1-TDO{slash}TRACESWO{slash}PB5-Pad37)") (class "Default")
      (node (ref "U1") (pin "37") (pinfunction "TDO/TRACESWO/PB5_37") (pintype "bidirectional"))
    )
    (net (code "67") (name "unconnected-(U1-TMS{slash}SWDIO{slash}PB6-Pad39)") (class "Default")
      (node (ref "U1") (pin "39") (pinfunction "TMS/SWDIO/PB6_39") (pintype "bidirectional"))
    )
    (net (code "68") (name "unconnected-(U1-TST-Pad30)") (class "Default")
      (node (ref "U1") (pin "30") (pinfunction "TST_30") (pintype "bidirectional"))
    )
    (net (code "69") (name "unconnected-(U2-PG-Pad8)") (class "Default")
      (node (ref "U2") (pin "8") (pinfunction "PG_8") (pintype "bidirectional"))
    )
  )
)
